# Printhead_contact_board.net
KiCad netlist of a schematic drawn in EAGLE
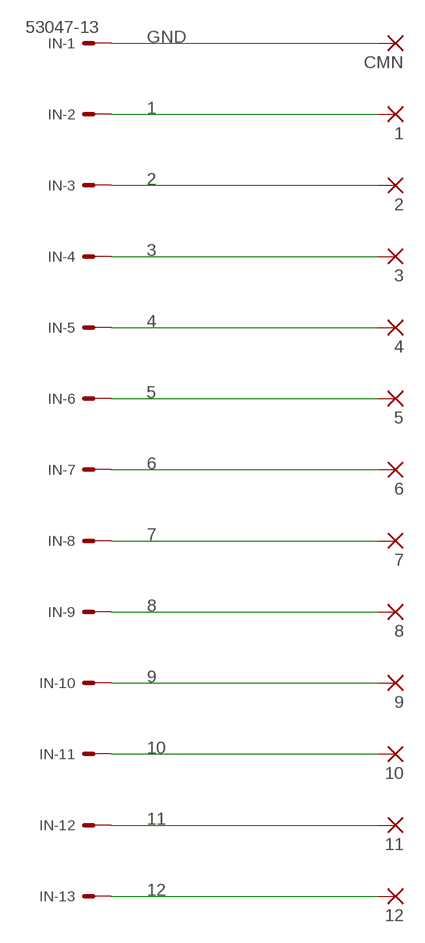
[diagram p0: schematic, sheet 1]

(export (version "E")
  (design (tool "Eeschema 10.0.6"))
  (components
    (comp (ref "1")
      (value "SMD2")
      (footprint "eagle-import:SMD1,27-2,54")
      (libsource (lib "eagle-import") (part "SMD2"))
    )
    (comp (ref "2")
      (value "SMD2")
      (footprint "eagle-import:SMD1,27-2,54")
      (libsource (lib "eagle-import") (part "SMD2"))
    )
    (comp (ref "3")
      (value "SMD2")
      (footprint "eagle-import:SMD1,27-2,54")
      (libsource (lib "eagle-import") (part "SMD2"))
    )
    (comp (ref "4")
      (value "SMD2")
      (footprint "eagle-import:SMD1,27-2,54")
      (libsource (lib "eagle-import") (part "SMD2"))
    )
    (comp (ref "5")
      (value "SMD2")
      (footprint "eagle-import:SMD1,27-2,54")
      (libsource (lib "eagle-import") (part "SMD2"))
    )
    (comp (ref "6")
      (value "SMD2")
      (footprint "eagle-import:SMD1,27-2,54")
      (libsource (lib "eagle-import") (part "SMD2"))
    )
    (comp (ref "7")
      (value "SMD2")
      (footprint "eagle-import:SMD1,27-2,54")
      (libsource (lib "eagle-import") (part "SMD2"))
    )
    (comp (ref "8")
      (value "SMD2")
      (footprint "eagle-import:SMD1,27-2,54")
      (libsource (lib "eagle-import") (part "SMD2"))
    )
    (comp (ref "9")
      (value "SMD2")
      (footprint "eagle-import:SMD1,27-2,54")
      (libsource (lib "eagle-import") (part "SMD2"))
    )
    (comp (ref "10")
      (value "SMD2")
      (footprint "eagle-import:SMD1,27-2,54")
      (libsource (lib "eagle-import") (part "SMD2"))
    )
    (comp (ref "11")
      (value "SMD2")
      (footprint "eagle-import:SMD1,27-2,54")
      (libsource (lib "eagle-import") (part "SMD2"))
    )
    (comp (ref "12")
      (value "SMD2")
      (footprint "eagle-import:SMD1,27-2,54")
      (libsource (lib "eagle-import") (part "SMD2"))
    )
    (comp (ref "CMN")
      (value "SMD2")
      (footprint "eagle-import:SMD1,27-2,54")
      (libsource (lib "eagle-import") (part "SMD2"))
    )
    (comp (ref "IN")
      (value "53047-13")
      (footprint "eagle-import:53047-13")
      (fields (field (name "MF") "MOLEX") (field (name "MPN") "53047-1310-C"))
      (libsource (lib "eagle-import") (part "53?-13047"))
    )
  )
  (nets
    (net (code "1") (name "/1") (class "Default")
      (node (ref "1") (pin "1") (pinfunction "P_1") (pintype "passive"))
      (node (ref "IN") (pin "2") (pinfunction "S_2") (pintype "passive"))
    )
    (net (code "2") (name "/2") (class "Default")
      (node (ref "2") (pin "1") (pinfunction "P_1") (pintype "passive"))
      (node (ref "IN") (pin "3") (pinfunction "S_3") (pintype "passive"))
    )
    (net (code "3") (name "/3") (class "Default")
      (node (ref "3") (pin "1") (pinfunction "P_1") (pintype "passive"))
      (node (ref "IN") (pin "4") (pinfunction "S_4") (pintype "passive"))
    )
    (net (code "4") (name "/4") (class "Default")
      (node (ref "4") (pin "1") (pinfunction "P_1") (pintype "passive"))
      (node (ref "IN") (pin "5") (pinfunction "S_5") (pintype "passive"))
    )
    (net (code "5") (name "/5") (class "Default")
      (node (ref "5") (pin "1") (pinfunction "P_1") (pintype "passive"))
      (node (ref "IN") (pin "6") (pinfunction "S_6") (pintype "passive"))
    )
    (net (code "6") (name "/6") (class "Default")
      (node (ref "6") (pin "1") (pinfunction "P_1") (pintype "passive"))
      (node (ref "IN") (pin "7") (pinfunction "S_7") (pintype "passive"))
    )
    (net (code "7") (name "/7") (class "Default")
      (node (ref "7") (pin "1") (pinfunction "P_1") (pintype "passive"))
      (node (ref "IN") (pin "8") (pinfunction "S_8") (pintype "passive"))
    )
    (net (code "8") (name "/8") (class "Default")
      (node (ref "8") (pin "1") (pinfunction "P_1") (pintype "passive"))
      (node (ref "IN") (pin "9") (pinfunction "S_9") (pintype "passive"))
    )
    (net (code "9") (name "/9") (class "Default")
      (node (ref "9") (pin "1") (pinfunction "P_1") (pintype "passive"))
      (node (ref "IN") (pin "10") (pinfunction "S_10") (pintype "passive"))
    )
    (net (code "10") (name "/10") (class "Default")
      (node (ref "10") (pin "1") (pinfunction "P_1") (pintype "passive"))
      (node (ref "IN") (pin "11") (pinfunction "S_11") (pintype "passive"))
    )
    (net (code "11") (name "/11") (class "Default")
      (node (ref "11") (pin "1") (pinfunction "P_1") (pintype "passive"))
      (node (ref "IN") (pin "12") (pinfunction "S_12") (pintype "passive"))
    )
    (net (code "12") (name "/12") (class "Default")
      (node (ref "12") (pin "1") (pinfunction "P_1") (pintype "passive"))
      (node (ref "IN") (pin "13") (pinfunction "S_13") (pintype "passive"))
    )
    (net (code "13") (name "/GND") (class "Default")
      (node (ref "CMN") (pin "1") (pinfunction "P_1") (pintype "passive"))
      (node (ref "IN") (pin "1") (pinfunction "S_1") (pintype "passive"))
    )
  )
)
